# Gym_rep_counter.net
KiCad netlist of a schematic drawn in Altium Designer
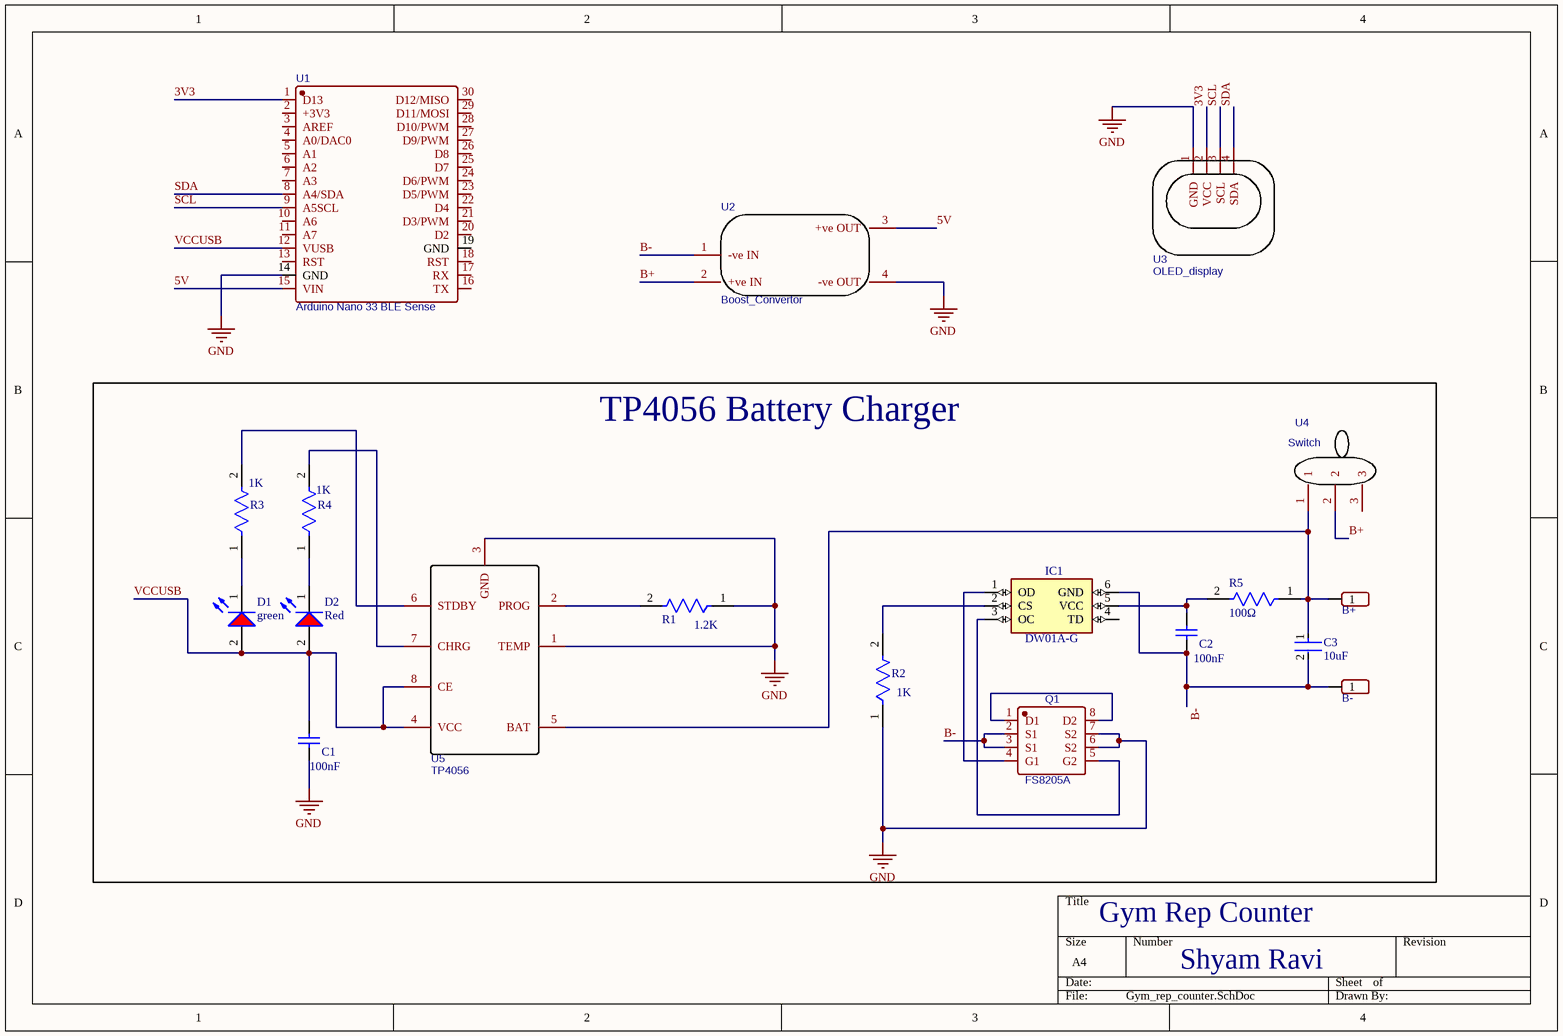
[diagram p0: Gym_rep_counter.SchDoc]

(export (version "E")
  (design (tool "Eeschema 10.0.6"))
  (components
    (comp (ref "B+")
      (value "Header-Male-2.54_1x1")
      (footprint "Battery_connector")
      (fields (field (name "MANUFACTURER") "ReliaPro"))
      (libsource (lib "Gym_rep_counter") (part "Battery_Connector"))
    )
    (comp (ref "B-")
      (value "Header-Male-2.54_1x1")
      (footprint "Battery_connector")
      (fields (field (name "MANUFACTURER") "ReliaPro"))
      (libsource (lib "Gym_rep_counter") (part "Battery_Connector"))
    )
    (comp (ref "C1")
      (value "100nF")
      (footprint "CAPC2013X88X50LL20T25")
      (fields (field (name "MANUFACTURER") "Kemet") (field (name "PART NUMBER") "C0805C103K5RACTU"))
      (libsource (lib "Altium Content Vault") (part "CAP"))
    )
    (comp (ref "C2")
      (value "100nF")
      (footprint "CAPC2013X88X50LL20T25")
      (fields (field (name "MANUFACTURER") "Kemet") (field (name "PART NUMBER") "C0805C103K5RACTU"))
      (libsource (lib "Altium Content Vault") (part "CAP"))
    )
    (comp (ref "C3")
      (value "10uF")
      (footprint "FP-GRM188-0_1-e0_2_0_5-IPC_B")
      (description "Chip Multilayer Ceramic Capacitors for General Purpose, 0603, 0.47uF, X7R, 15%, 10%, 16V")
      (fields (field (name "VOLTAGE") "16V") (field (name "TOLERANCE") "10%"))
      (libsource (lib "Altium Content Vault") (part "11868f565c42a9108669ba33697ecf6"))
    )
    (comp (ref "D1")
      (value "green")
      (footprint "WL-SMCW_0805_150080xx75000")
      (description "LED Uni-Color Red 630nm 2-Pin Chip 0805(2012Metric) T/R")
      (libsource (lib "Altium Content Vault") (part "LED_Red_2A-1K"))
    )
    (comp (ref "D2")
      (value "Red")
      (footprint "WL-SMCW_0805_150080xx75000")
      (description "LED Uni-Color Red 630nm 2-Pin Chip 0805(2012Metric) T/R")
      (libsource (lib "Altium Content Vault") (part "LED_Red_2A-1K"))
    )
    (comp (ref "IC1")
      (value "DW01A-G")
      (footprint "SOT95P280X135-6N")
      (description "One Cell Lithium-ion/Polymer Battery Protection IC")
      (fields (field (name "MF") "Fortune"))
      (libsource (lib "DW01A-G") (part "DW01A-G"))
    )
    (comp (ref "Q1")
      (value "FS8205A")
      (footprint "TSSOP-8_L4.4-W3.5-P0.65-LS6.4-BL")
      (fields (field (name "MANUFACTURER") "FORTUNE"))
      (libsource (lib "Gym_rep_counter") (part "FS8205A"))
    )
    (comp (ref "R1")
      (value "1.2K")
      (footprint "FP-CRCW0603-HPe3-MFG")
      (description "RES Thick Film, 1kΩ, 1%, 0.33W, 100ppm/°C, 0603")
      (fields (field (name "TOLERANCE") "1%"))
      (libsource (lib "Altium Content Vault") (part "1029c3af85768c4190bb7ad29bc67b5"))
    )
    (comp (ref "R2")
      (value "1K")
      (footprint "FP-CRCW0603-HPe3-MFG")
      (description "RES Thick Film, 1kΩ, 1%, 0.33W, 100ppm/°C, 0603")
      (fields (field (name "TOLERANCE") "1%"))
      (libsource (lib "Altium Content Vault") (part "1029c3af85768c4190bb7ad29bc67b5"))
    )
    (comp (ref "R3")
      (value "1K")
      (footprint "FP-CRCW0603-HPe3-MFG")
      (description "RES Thick Film, 1kΩ, 1%, 0.33W, 100ppm/°C, 0603")
      (fields (field (name "TOLERANCE") "1%"))
      (libsource (lib "Altium Content Vault") (part "1029c3af85768c4190bb7ad29bc67b5"))
    )
    (comp (ref "R4")
      (value "1K")
      (footprint "FP-CRCW0603-HPe3-MFG")
      (description "RES Thick Film, 1kΩ, 1%, 0.33W, 100ppm/°C, 0603")
      (fields (field (name "TOLERANCE") "1%"))
      (libsource (lib "Altium Content Vault") (part "1029c3af85768c4190bb7ad29bc67b5"))
    )
    (comp (ref "R5")
      (value "100Ω")
      (footprint "FP-CRCW0603-HPe3-MFG")
      (description "RES Thick Film, 1kΩ, 1%, 0.33W, 100ppm/°C, 0603")
      (fields (field (name "TOLERANCE") "1%"))
      (libsource (lib "Altium Content Vault") (part "1029c3af85768c4190bb7ad29bc67b5"))
    )
    (comp (ref "U1")
      (value "Arduino Nano 33 BLE Sense")
      (footprint "arduino_nano_33")
      (fields
        (field (name "MANUFACTURER") "Arduino")
        (field (name "MANUFACTURER PART") "Barcode: 7630049201507")
        (field (name "CONTRIBUTOR") "RedCoal")
      )
      (libsource (lib "Gym_rep_counter") (part "arduino_nano_33"))
    )
    (comp (ref "U2")
      (value "Boost_Convertor")
      (footprint "BOOST_CONVERTER")
      (fields (field (name "CONTRIBUTOR") "Shyam Ravi"))
      (libsource (lib "Gym_rep_counter") (part "Boost_Convertor"))
    )
    (comp (ref "U3")
      (value "OLED_display")
      (footprint "OLED_DISPLAY")
      (fields (field (name "CONTRIBUTOR") "shyamganeshravi2003"))
      (libsource (lib "Gym_rep_counter") (part "OLED_display"))
    )
    (comp (ref "U4")
      (value "Switch")
      (footprint "SWITCH")
      (fields (field (name "CONTRIBUTOR") "Shyam Ravi"))
      (libsource (lib "Gym_rep_counter") (part "Switch"))
    )
    (comp (ref "U5")
      (value "TP4056")
      (footprint "TP4056")
      (fields (field (name "MANUFACTURER") "TOPPOWER") (field (name "CONTRIBUTOR") "Guest"))
      (libsource (lib "Gym_rep_counter") (part "TP4056"))
    )
  )
  (nets
    (net (code "1") (name "/3V3") (class "Default")
      (node (ref "U1") (pin "1") (pinfunction "D13_1") (pintype "passive"))
      (node (ref "U3") (pin "2") (pinfunction "VCC_2") (pintype "passive"))
    )
    (net (code "2") (name "/5V") (class "Default")
      (node (ref "U1") (pin "15") (pinfunction "VIN_15") (pintype "passive"))
      (node (ref "U2") (pin "3") (pinfunction "+ve_OUT_3") (pintype "passive"))
    )
    (net (code "3") (name "/B+") (class "Default")
      (node (ref "U2") (pin "2") (pinfunction "+ve_IN_2") (pintype "passive"))
      (node (ref "U4") (pin "2") (pinfunction "2_2") (pintype "passive"))
    )
    (net (code "4") (name "/B-") (class "Default")
      (node (ref "B-") (pin "1") (pinfunction "1_1") (pintype "passive"))
      (node (ref "C2") (pin "1") (pinfunction "1_1") (pintype "passive"))
      (node (ref "C3") (pin "2") (pinfunction "2_2") (pintype "passive"))
      (node (ref "IC1") (pin "6") (pinfunction "GND_6") (pintype "bidirectional"))
      (node (ref "Q1") (pin "2") (pinfunction "S1_2") (pintype "passive"))
      (node (ref "Q1") (pin "3") (pinfunction "S1_3") (pintype "passive"))
      (node (ref "U2") (pin "1") (pinfunction "-ve_IN_1") (pintype "passive"))
    )
    (net (code "5") (name "/SCL") (class "Default")
      (node (ref "U1") (pin "9") (pinfunction "A5SCL_9") (pintype "passive"))
      (node (ref "U3") (pin "3") (pinfunction "SCL_3") (pintype "passive"))
    )
    (net (code "6") (name "/SDA") (class "Default")
      (node (ref "U1") (pin "8") (pinfunction "A4/SDA_8") (pintype "passive"))
      (node (ref "U3") (pin "4") (pinfunction "SDA_4") (pintype "passive"))
    )
    (net (code "7") (name "/VCCUSB") (class "Default")
      (node (ref "C1") (pin "2") (pinfunction "2_2") (pintype "passive"))
      (node (ref "D1") (pin "2") (pinfunction "A_2") (pintype "passive"))
      (node (ref "D2") (pin "2") (pinfunction "A_2") (pintype "passive"))
      (node (ref "U1") (pin "12") (pinfunction "VUSB_12") (pintype "passive"))
      (node (ref "U5") (pin "4") (pinfunction "VCC_4") (pintype "passive"))
      (node (ref "U5") (pin "8") (pinfunction "CE_8") (pintype "passive"))
    )
    (net (code "8") (name "GND") (class "Default")
      (node (ref "C1") (pin "1") (pinfunction "1_1") (pintype "passive"))
      (node (ref "Q1") (pin "6") (pinfunction "S2_6") (pintype "passive"))
      (node (ref "Q1") (pin "7") (pinfunction "S2_7") (pintype "passive"))
      (node (ref "R1") (pin "1") (pinfunction "1_1") (pintype "passive"))
      (node (ref "R2") (pin "1") (pinfunction "1_1") (pintype "passive"))
      (node (ref "U1") (pin "14") (pinfunction "GND_14") (pintype "passive"))
      (node (ref "U2") (pin "4") (pinfunction "-ve_OUT_4") (pintype "passive"))
      (node (ref "U3") (pin "1") (pinfunction "GND_1") (pintype "passive"))
      (node (ref "U5") (pin "1") (pinfunction "TEMP_1") (pintype "passive"))
      (node (ref "U5") (pin "3") (pinfunction "GND_3") (pintype "passive"))
    )
    (net (code "9") (name "Net-(D1-K)") (class "Default")
      (node (ref "D1") (pin "1") (pinfunction "K_1") (pintype "passive"))
      (node (ref "R3") (pin "1") (pinfunction "1_1") (pintype "passive"))
    )
    (net (code "10") (name "Net-(D2-K)") (class "Default")
      (node (ref "D2") (pin "1") (pinfunction "K_1") (pintype "passive"))
      (node (ref "R4") (pin "1") (pinfunction "1_1") (pintype "passive"))
    )
    (net (code "11") (name "Net-(IC1-CS)") (class "Default")
      (node (ref "IC1") (pin "2") (pinfunction "CS_2") (pintype "bidirectional"))
      (node (ref "R2") (pin "2") (pinfunction "2_2") (pintype "passive"))
    )
    (net (code "12") (name "Net-(IC1-OC)") (class "Default")
      (node (ref "IC1") (pin "3") (pinfunction "OC_3") (pintype "bidirectional"))
      (node (ref "Q1") (pin "5") (pinfunction "G2_5") (pintype "passive"))
    )
    (net (code "13") (name "Net-(IC1-OD)") (class "Default")
      (node (ref "IC1") (pin "1") (pinfunction "OD_1") (pintype "bidirectional"))
      (node (ref "Q1") (pin "4") (pinfunction "G1_4") (pintype "passive"))
    )
    (net (code "14") (name "Net-(IC1-VCC)") (class "Default")
      (node (ref "C2") (pin "2") (pinfunction "2_2") (pintype "passive"))
      (node (ref "IC1") (pin "5") (pinfunction "VCC_5") (pintype "bidirectional"))
      (node (ref "R5") (pin "2") (pinfunction "2_2") (pintype "passive"))
    )
    (net (code "15") (name "Net-(Q1-D1)") (class "Default")
      (node (ref "Q1") (pin "1") (pinfunction "D1_1") (pintype "passive"))
      (node (ref "Q1") (pin "8") (pinfunction "D2_8") (pintype "passive"))
    )
    (net (code "16") (name "Net-(U5-BAT)") (class "Default")
      (node (ref "B+") (pin "1") (pinfunction "1_1") (pintype "passive"))
      (node (ref "C3") (pin "1") (pinfunction "1_1") (pintype "passive"))
      (node (ref "R5") (pin "1") (pinfunction "1_1") (pintype "passive"))
      (node (ref "U4") (pin "1") (pinfunction "1_1") (pintype "passive"))
      (node (ref "U5") (pin "5") (pinfunction "BAT_5") (pintype "passive"))
    )
    (net (code "17") (name "Net-(U5-CHRG)") (class "Default")
      (node (ref "R4") (pin "2") (pinfunction "2_2") (pintype "passive"))
      (node (ref "U5") (pin "7") (pinfunction "CHRG_7") (pintype "passive"))
    )
    (net (code "18") (name "Net-(U5-PROG)") (class "Default")
      (node (ref "R1") (pin "2") (pinfunction "2_2") (pintype "passive"))
      (node (ref "U5") (pin "2") (pinfunction "PROG_2") (pintype "passive"))
    )
    (net (code "19") (name "Net-(U5-STDBY)") (class "Default")
      (node (ref "R3") (pin "2") (pinfunction "2_2") (pintype "passive"))
      (node (ref "U5") (pin "6") (pinfunction "STDBY_6") (pintype "passive"))
    )
    (net (code "20") (name "unconnected-(IC1-TD-Pad4)") (class "Default")
      (node (ref "IC1") (pin "4") (pinfunction "TD_4") (pintype "bidirectional"))
    )
    (net (code "21") (name "unconnected-(U1-+3V3-Pad2)") (class "Default")
      (node (ref "U1") (pin "2") (pinfunction "+3V3_2") (pintype "passive"))
    )
    (net (code "22") (name "unconnected-(U1-A0{slash}DAC0-Pad4)") (class "Default")
      (node (ref "U1") (pin "4") (pinfunction "A0/DAC0_4") (pintype "passive"))
    )
    (net (code "23") (name "unconnected-(U1-A1-Pad5)") (class "Default")
      (node (ref "U1") (pin "5") (pinfunction "A1_5") (pintype "passive"))
    )
    (net (code "24") (name "unconnected-(U1-A2-Pad6)") (class "Default")
      (node (ref "U1") (pin "6") (pinfunction "A2_6") (pintype "passive"))
    )
    (net (code "25") (name "unconnected-(U1-A3-Pad7)") (class "Default")
      (node (ref "U1") (pin "7") (pinfunction "A3_7") (pintype "passive"))
    )
    (net (code "26") (name "unconnected-(U1-A6-Pad10)") (class "Default")
      (node (ref "U1") (pin "10") (pinfunction "A6_10") (pintype "passive"))
    )
    (net (code "27") (name "unconnected-(U1-A7-Pad11)") (class "Default")
      (node (ref "U1") (pin "11") (pinfunction "A7_11") (pintype "passive"))
    )
    (net (code "28") (name "unconnected-(U1-AREF-Pad3)") (class "Default")
      (node (ref "U1") (pin "3") (pinfunction "AREF_3") (pintype "passive"))
    )
    (net (code "29") (name "unconnected-(U1-D2-Pad20)") (class "Default")
      (node (ref "U1") (pin "20") (pinfunction "D2_20") (pintype "passive"))
    )
    (net (code "30") (name "unconnected-(U1-D3{slash}PWM-Pad21)") (class "Default")
      (node (ref "U1") (pin "21") (pinfunction "D3/PWM_21") (pintype "passive"))
    )
    (net (code "31") (name "unconnected-(U1-D4-Pad22)") (class "Default")
      (node (ref "U1") (pin "22") (pinfunction "D4_22") (pintype "passive"))
    )
    (net (code "32") (name "unconnected-(U1-D5{slash}PWM-Pad23)") (class "Default")
      (node (ref "U1") (pin "23") (pinfunction "D5/PWM_23") (pintype "passive"))
    )
    (net (code "33") (name "unconnected-(U1-D6{slash}PWM-Pad24)") (class "Default")
      (node (ref "U1") (pin "24") (pinfunction "D6/PWM_24") (pintype "passive"))
    )
    (net (code "34") (name "unconnected-(U1-D7-Pad25)") (class "Default")
      (node (ref "U1") (pin "25") (pinfunction "D7_25") (pintype "passive"))
    )
    (net (code "35") (name "unconnected-(U1-D8-Pad26)") (class "Default")
      (node (ref "U1") (pin "26") (pinfunction "D8_26") (pintype "passive"))
    )
    (net (code "36") (name "unconnected-(U1-D9{slash}PWM-Pad27)") (class "Default")
      (node (ref "U1") (pin "27") (pinfunction "D9/PWM_27") (pintype "passive"))
    )
    (net (code "37") (name "unconnected-(U1-D10{slash}PWM-Pad28)") (class "Default")
      (node (ref "U1") (pin "28") (pinfunction "D10/PWM_28") (pintype "passive"))
    )
    (net (code "38") (name "unconnected-(U1-D11{slash}MOSI-Pad29)") (class "Default")
      (node (ref "U1") (pin "29") (pinfunction "D11/MOSI_29") (pintype "passive"))
    )
    (net (code "39") (name "unconnected-(U1-D12{slash}MISO-Pad30)") (class "Default")
      (node (ref "U1") (pin "30") (pinfunction "D12/MISO_30") (pintype "passive"))
    )
    (net (code "40") (name "unconnected-(U1-GND-Pad19)") (class "Default")
      (node (ref "U1") (pin "19") (pinfunction "GND_19") (pintype "passive"))
    )
    (net (code "41") (name "unconnected-(U1-RST-Pad13)") (class "Default")
      (node (ref "U1") (pin "13") (pinfunction "RST_13") (pintype "passive"))
    )
    (net (code "42") (name "unconnected-(U1-RST-Pad18)") (class "Default")
      (node (ref "U1") (pin "18") (pinfunction "RST_18") (pintype "passive"))
    )
    (net (code "43") (name "unconnected-(U1-RX-Pad17)") (class "Default")
      (node (ref "U1") (pin "17") (pinfunction "RX_17") (pintype "passive"))
    )
    (net (code "44") (name "unconnected-(U1-TX-Pad16)") (class "Default")
      (node (ref "U1") (pin "16") (pinfunction "TX_16") (pintype "passive"))
    )
    (net (code "45") (name "unconnected-(U4-Pad3)") (class "Default")
      (node (ref "U4") (pin "3") (pinfunction "3_3") (pintype "passive"))
    )
  )
)
